# suPino.net
KiCad netlist of a schematic drawn in EAGLE
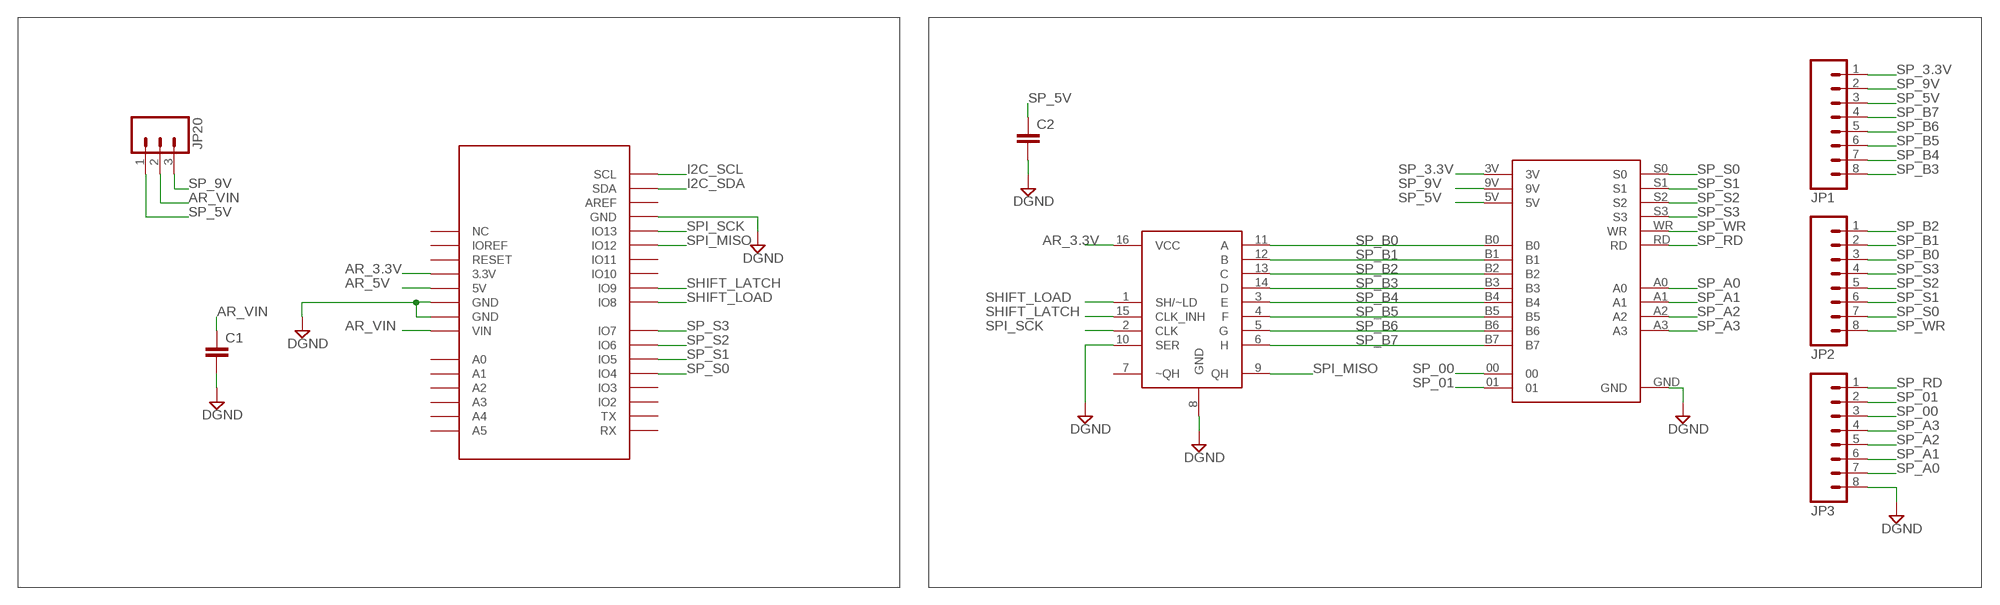
[diagram p0: schematic, sheet 1, part 1 of 2]
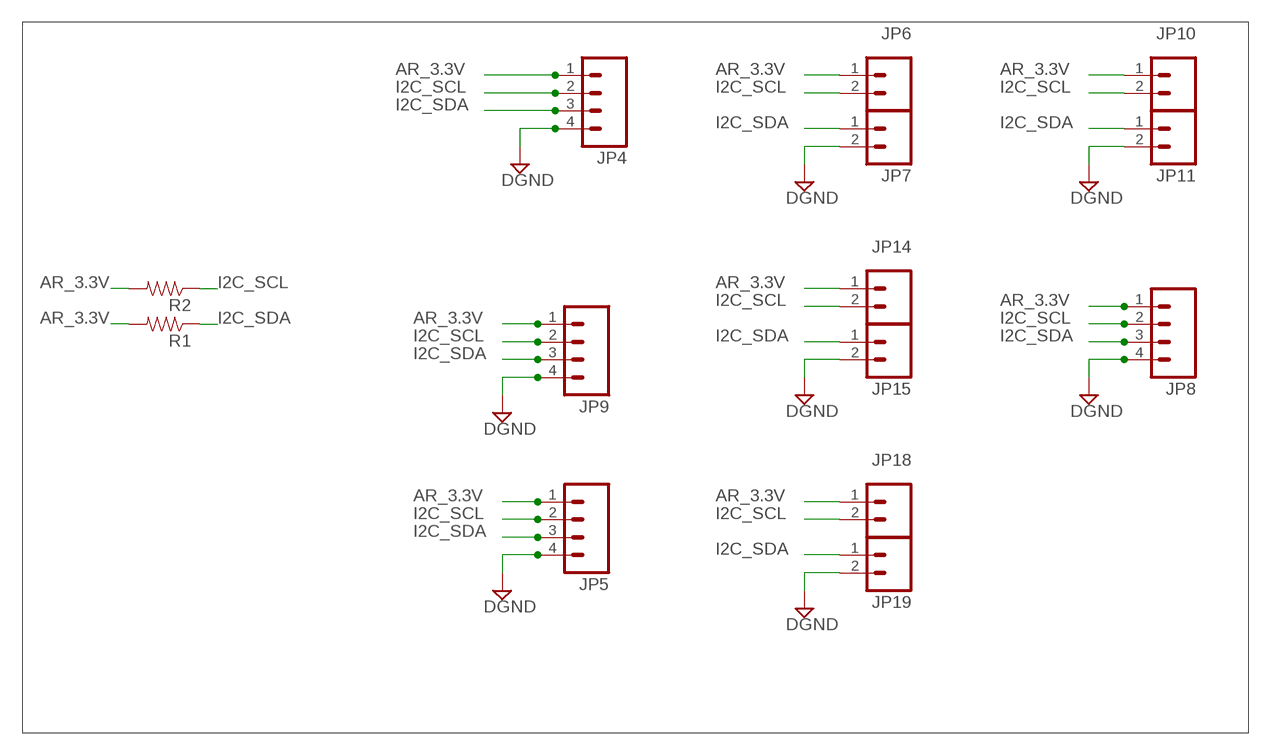
[diagram p1: schematic, sheet 1, part 2 of 2]

(export (version "E")
  (design (tool "Eeschema 10.0.6"))
  (components
    (comp (ref "C1")
      (value "CAP0805")
      (footprint "eagle-import:0805")
      (libsource (lib "eagle-import") (part "CAP0805"))
    )
    (comp (ref "C2")
      (value "CAP0805")
      (footprint "eagle-import:0805")
      (libsource (lib "eagle-import") (part "CAP0805"))
    )
    (comp (ref "JP1")
      (value "M08")
      (footprint "eagle-import:1X08_ROUND")
      (libsource (lib "eagle-import") (part "M08"))
    )
    (comp (ref "JP2")
      (value "M08")
      (footprint "eagle-import:1X08_ROUND")
      (libsource (lib "eagle-import") (part "M08"))
    )
    (comp (ref "JP3")
      (value "M08")
      (footprint "eagle-import:1X08_ROUND")
      (libsource (lib "eagle-import") (part "M08"))
    )
    (comp (ref "JP4")
      (value "M04PTH")
      (footprint "eagle-import:1X04")
      (libsource (lib "eagle-import") (part "M04PTH"))
    )
    (comp (ref "JP5")
      (value "M04PTH")
      (footprint "eagle-import:1X04")
      (libsource (lib "eagle-import") (part "M04PTH"))
    )
    (comp (ref "JP6")
      (value "M023.5MM")
      (footprint "eagle-import:SCREWTERMINAL-3.5MM-2")
      (libsource (lib "eagle-import") (part "M023.5MM"))
    )
    (comp (ref "JP7")
      (value "M023.5MM")
      (footprint "eagle-import:SCREWTERMINAL-3.5MM-2")
      (libsource (lib "eagle-import") (part "M023.5MM"))
    )
    (comp (ref "JP8")
      (value "M04PTH")
      (footprint "eagle-import:1X04")
      (libsource (lib "eagle-import") (part "M04PTH"))
    )
    (comp (ref "JP9")
      (value "M04PTH")
      (footprint "eagle-import:1X04")
      (libsource (lib "eagle-import") (part "M04PTH"))
    )
    (comp (ref "JP10")
      (value "M023.5MM")
      (footprint "eagle-import:SCREWTERMINAL-3.5MM-2")
      (libsource (lib "eagle-import") (part "M023.5MM"))
    )
    (comp (ref "JP11")
      (value "M023.5MM")
      (footprint "eagle-import:SCREWTERMINAL-3.5MM-2")
      (libsource (lib "eagle-import") (part "M023.5MM"))
    )
    (comp (ref "JP14")
      (value "M023.5MM")
      (footprint "eagle-import:SCREWTERMINAL-3.5MM-2")
      (libsource (lib "eagle-import") (part "M023.5MM"))
    )
    (comp (ref "JP15")
      (value "M023.5MM")
      (footprint "eagle-import:SCREWTERMINAL-3.5MM-2")
      (libsource (lib "eagle-import") (part "M023.5MM"))
    )
    (comp (ref "JP18")
      (value "M023.5MM")
      (footprint "eagle-import:SCREWTERMINAL-3.5MM-2")
      (libsource (lib "eagle-import") (part "M023.5MM"))
    )
    (comp (ref "JP19")
      (value "M023.5MM")
      (footprint "eagle-import:SCREWTERMINAL-3.5MM-2")
      (libsource (lib "eagle-import") (part "M023.5MM"))
    )
    (comp (ref "JP20")
      (value "M03PTH")
      (footprint "eagle-import:1X03")
      (libsource (lib "eagle-import") (part "M03PTH"))
    )
    (comp (ref "R1")
      (value "RESISTOR0805-RES")
      (footprint "eagle-import:0805")
      (libsource (lib "eagle-import") (part "RESISTOR0805-RES"))
    )
    (comp (ref "R2")
      (value "RESISTOR0805-RES")
      (footprint "eagle-import:0805")
      (libsource (lib "eagle-import") (part "RESISTOR0805-RES"))
    )
    (comp (ref "U$1")
      (value "ARDUIN_SHIELD")
      (footprint "eagle-import:ARDUNIO_SHIELD")
      (libsource (lib "eagle-import") (part "ARDUIN_SHIELD"))
    )
    (comp (ref "U$2")
      (value "SUPERPRO_BOARD")
      (footprint "eagle-import:SUPERPRO_BOARD")
      (libsource (lib "eagle-import") (part "SUPERPRO_BOARD"))
    )
    (comp (ref "U$4")
      (value "8B_SHIFT_REG")
      (footprint "eagle-import:TSSOP16")
      (libsource (lib "eagle-import") (part "8B_SHIFT_REG"))
    )
  )
  (nets
    (net (code "1") (name "/AR_3.3V") (class "Default")
      (node (ref "JP10") (pin "1") (pinfunction "1_1") (pintype "passive"))
      (node (ref "JP14") (pin "1") (pinfunction "1_1") (pintype "passive"))
      (node (ref "JP18") (pin "1") (pinfunction "1_1") (pintype "passive"))
      (node (ref "JP4") (pin "1") (pinfunction "1_1") (pintype "passive"))
      (node (ref "JP5") (pin "1") (pinfunction "1_1") (pintype "passive"))
      (node (ref "JP6") (pin "1") (pinfunction "1_1") (pintype "passive"))
      (node (ref "JP8") (pin "1") (pinfunction "1_1") (pintype "passive"))
      (node (ref "JP9") (pin "1") (pinfunction "1_1") (pintype "passive"))
      (node (ref "R1") (pin "2") (pinfunction "2_2") (pintype "passive"))
      (node (ref "R2") (pin "2") (pinfunction "2_2") (pintype "passive"))
      (node (ref "U$1") (pin "3.3V") (pinfunction "3.3V_3.3V") (pintype "bidirectional"))
      (node (ref "U$4") (pin "16") (pinfunction "VCC_16") (pintype "bidirectional"))
    )
    (net (code "2") (name "/AR_5V") (class "Default")
      (node (ref "U$1") (pin "5V") (pinfunction "5V_5V") (pintype "bidirectional"))
    )
    (net (code "3") (name "/AR_VIN") (class "Default")
      (node (ref "C1") (pin "1") (pinfunction "1_1") (pintype "passive"))
      (node (ref "JP20") (pin "2") (pinfunction "2_2") (pintype "passive"))
      (node (ref "U$1") (pin "VIN") (pinfunction "VIN_VIN") (pintype "bidirectional"))
    )
    (net (code "4") (name "/I2C_SCL") (class "Default")
      (node (ref "JP10") (pin "2") (pinfunction "2_2") (pintype "passive"))
      (node (ref "JP14") (pin "2") (pinfunction "2_2") (pintype "passive"))
      (node (ref "JP18") (pin "2") (pinfunction "2_2") (pintype "passive"))
      (node (ref "JP4") (pin "2") (pinfunction "2_2") (pintype "passive"))
      (node (ref "JP5") (pin "2") (pinfunction "2_2") (pintype "passive"))
      (node (ref "JP6") (pin "2") (pinfunction "2_2") (pintype "passive"))
      (node (ref "JP8") (pin "2") (pinfunction "2_2") (pintype "passive"))
      (node (ref "JP9") (pin "2") (pinfunction "2_2") (pintype "passive"))
      (node (ref "R2") (pin "1") (pinfunction "1_1") (pintype "passive"))
      (node (ref "U$1") (pin "SCL") (pinfunction "SCL_SCL") (pintype "bidirectional"))
    )
    (net (code "5") (name "/I2C_SDA") (class "Default")
      (node (ref "JP11") (pin "1") (pinfunction "1_1") (pintype "passive"))
      (node (ref "JP15") (pin "1") (pinfunction "1_1") (pintype "passive"))
      (node (ref "JP19") (pin "1") (pinfunction "1_1") (pintype "passive"))
      (node (ref "JP4") (pin "3") (pinfunction "3_3") (pintype "passive"))
      (node (ref "JP5") (pin "3") (pinfunction "3_3") (pintype "passive"))
      (node (ref "JP7") (pin "1") (pinfunction "1_1") (pintype "passive"))
      (node (ref "JP8") (pin "3") (pinfunction "3_3") (pintype "passive"))
      (node (ref "JP9") (pin "3") (pinfunction "3_3") (pintype "passive"))
      (node (ref "R1") (pin "1") (pinfunction "1_1") (pintype "passive"))
      (node (ref "U$1") (pin "SDA") (pinfunction "SDA_SDA") (pintype "bidirectional"))
    )
    (net (code "6") (name "/SHIFT_LATCH") (class "Default")
      (node (ref "U$1") (pin "IO9") (pinfunction "IO9_IO9") (pintype "bidirectional"))
      (node (ref "U$4") (pin "15") (pinfunction "CLK_INH_15") (pintype "bidirectional"))
    )
    (net (code "7") (name "/SHIFT_LOAD") (class "Default")
      (node (ref "U$1") (pin "IO8") (pinfunction "IO8_IO8") (pintype "bidirectional"))
      (node (ref "U$4") (pin "1") (pinfunction "SH/~{LD}_1") (pintype "bidirectional"))
    )
    (net (code "8") (name "/SPI_MISO") (class "Default")
      (node (ref "U$1") (pin "IO12") (pinfunction "IO12_IO12") (pintype "bidirectional"))
      (node (ref "U$4") (pin "9") (pinfunction "QH_9") (pintype "bidirectional"))
    )
    (net (code "9") (name "/SPI_SCK") (class "Default")
      (node (ref "U$1") (pin "IO13") (pinfunction "IO13_IO13") (pintype "bidirectional"))
      (node (ref "U$4") (pin "2") (pinfunction "CLK_2") (pintype "bidirectional"))
    )
    (net (code "10") (name "/SP_00") (class "Default")
      (node (ref "JP3") (pin "3") (pinfunction "3_3") (pintype "passive"))
      (node (ref "U$2") (pin "00") (pinfunction "00_00") (pintype "bidirectional"))
    )
    (net (code "11") (name "/SP_01") (class "Default")
      (node (ref "JP3") (pin "2") (pinfunction "2_2") (pintype "passive"))
      (node (ref "U$2") (pin "01") (pinfunction "01_01") (pintype "bidirectional"))
    )
    (net (code "12") (name "/SP_3.3V") (class "Default")
      (node (ref "JP1") (pin "1") (pinfunction "1_1") (pintype "passive"))
      (node (ref "U$2") (pin "3V") (pinfunction "3V_3V") (pintype "bidirectional"))
    )
    (net (code "13") (name "/SP_5V") (class "Default")
      (node (ref "C2") (pin "1") (pinfunction "1_1") (pintype "passive"))
      (node (ref "JP1") (pin "3") (pinfunction "3_3") (pintype "passive"))
      (node (ref "JP20") (pin "1") (pinfunction "1_1") (pintype "passive"))
      (node (ref "U$2") (pin "5V") (pinfunction "5V_5V") (pintype "bidirectional"))
    )
    (net (code "14") (name "/SP_9V") (class "Default")
      (node (ref "JP1") (pin "2") (pinfunction "2_2") (pintype "passive"))
      (node (ref "JP20") (pin "3") (pinfunction "3_3") (pintype "passive"))
      (node (ref "U$2") (pin "9V") (pinfunction "9V_9V") (pintype "bidirectional"))
    )
    (net (code "15") (name "/SP_A0") (class "Default")
      (node (ref "JP3") (pin "7") (pinfunction "7_7") (pintype "passive"))
      (node (ref "U$2") (pin "A0") (pinfunction "A0_A0") (pintype "bidirectional"))
    )
    (net (code "16") (name "/SP_A1") (class "Default")
      (node (ref "JP3") (pin "6") (pinfunction "6_6") (pintype "passive"))
      (node (ref "U$2") (pin "A1") (pinfunction "A1_A1") (pintype "bidirectional"))
    )
    (net (code "17") (name "/SP_A2") (class "Default")
      (node (ref "JP3") (pin "5") (pinfunction "5_5") (pintype "passive"))
      (node (ref "U$2") (pin "A2") (pinfunction "A2_A2") (pintype "bidirectional"))
    )
    (net (code "18") (name "/SP_A3") (class "Default")
      (node (ref "JP3") (pin "4") (pinfunction "4_4") (pintype "passive"))
      (node (ref "U$2") (pin "A3") (pinfunction "A3_A3") (pintype "bidirectional"))
    )
    (net (code "19") (name "/SP_B0") (class "Default")
      (node (ref "JP2") (pin "3") (pinfunction "3_3") (pintype "passive"))
      (node (ref "U$2") (pin "B0") (pinfunction "B0_B0") (pintype "bidirectional"))
      (node (ref "U$4") (pin "11") (pinfunction "A_11") (pintype "bidirectional"))
    )
    (net (code "20") (name "/SP_B1") (class "Default")
      (node (ref "JP2") (pin "2") (pinfunction "2_2") (pintype "passive"))
      (node (ref "U$2") (pin "B1") (pinfunction "B1_B1") (pintype "bidirectional"))
      (node (ref "U$4") (pin "12") (pinfunction "B_12") (pintype "bidirectional"))
    )
    (net (code "21") (name "/SP_B2") (class "Default")
      (node (ref "JP2") (pin "1") (pinfunction "1_1") (pintype "passive"))
      (node (ref "U$2") (pin "B2") (pinfunction "B2_B2") (pintype "bidirectional"))
      (node (ref "U$4") (pin "13") (pinfunction "C_13") (pintype "bidirectional"))
    )
    (net (code "22") (name "/SP_B3") (class "Default")
      (node (ref "JP1") (pin "8") (pinfunction "8_8") (pintype "passive"))
      (node (ref "U$2") (pin "B3") (pinfunction "B3_B3") (pintype "bidirectional"))
      (node (ref "U$4") (pin "14") (pinfunction "D_14") (pintype "bidirectional"))
    )
    (net (code "23") (name "/SP_B4") (class "Default")
      (node (ref "JP1") (pin "7") (pinfunction "7_7") (pintype "passive"))
      (node (ref "U$2") (pin "B4") (pinfunction "B4_B4") (pintype "bidirectional"))
      (node (ref "U$4") (pin "3") (pinfunction "E_3") (pintype "bidirectional"))
    )
    (net (code "24") (name "/SP_B5") (class "Default")
      (node (ref "JP1") (pin "6") (pinfunction "6_6") (pintype "passive"))
      (node (ref "U$2") (pin "B5") (pinfunction "B5_B5") (pintype "bidirectional"))
      (node (ref "U$4") (pin "4") (pinfunction "F_4") (pintype "bidirectional"))
    )
    (net (code "25") (name "/SP_B6") (class "Default")
      (node (ref "JP1") (pin "5") (pinfunction "5_5") (pintype "passive"))
      (node (ref "U$2") (pin "B6") (pinfunction "B6_B6") (pintype "bidirectional"))
      (node (ref "U$4") (pin "5") (pinfunction "G_5") (pintype "bidirectional"))
    )
    (net (code "26") (name "/SP_B7") (class "Default")
      (node (ref "JP1") (pin "4") (pinfunction "4_4") (pintype "passive"))
      (node (ref "U$2") (pin "B7") (pinfunction "B7_B7") (pintype "bidirectional"))
      (node (ref "U$4") (pin "6") (pinfunction "H_6") (pintype "bidirectional"))
    )
    (net (code "27") (name "/SP_RD") (class "Default")
      (node (ref "JP3") (pin "1") (pinfunction "1_1") (pintype "passive"))
      (node (ref "U$2") (pin "RD") (pinfunction "RD_RD") (pintype "bidirectional"))
    )
    (net (code "28") (name "/SP_S0") (class "Default")
      (node (ref "JP2") (pin "7") (pinfunction "7_7") (pintype "passive"))
      (node (ref "U$1") (pin "IO4") (pinfunction "IO4_IO4") (pintype "bidirectional"))
      (node (ref "U$2") (pin "S0") (pinfunction "S0_S0") (pintype "bidirectional"))
    )
    (net (code "29") (name "/SP_S1") (class "Default")
      (node (ref "JP2") (pin "6") (pinfunction "6_6") (pintype "passive"))
      (node (ref "U$1") (pin "IO5") (pinfunction "IO5_IO5") (pintype "bidirectional"))
      (node (ref "U$2") (pin "S1") (pinfunction "S1_S1") (pintype "bidirectional"))
    )
    (net (code "30") (name "/SP_S2") (class "Default")
      (node (ref "JP2") (pin "5") (pinfunction "5_5") (pintype "passive"))
      (node (ref "U$1") (pin "IO6") (pinfunction "IO6_IO6") (pintype "bidirectional"))
      (node (ref "U$2") (pin "S2") (pinfunction "S2_S2") (pintype "bidirectional"))
    )
    (net (code "31") (name "/SP_S3") (class "Default")
      (node (ref "JP2") (pin "4") (pinfunction "4_4") (pintype "passive"))
      (node (ref "U$1") (pin "IO7") (pinfunction "IO7_IO7") (pintype "bidirectional"))
      (node (ref "U$2") (pin "S3") (pinfunction "S3_S3") (pintype "bidirectional"))
    )
    (net (code "32") (name "/SP_WR") (class "Default")
      (node (ref "JP2") (pin "8") (pinfunction "8_8") (pintype "passive"))
      (node (ref "U$2") (pin "WR") (pinfunction "WR_WR") (pintype "bidirectional"))
    )
    (net (code "33") (name "DGND") (class "Default")
      (node (ref "C1") (pin "2") (pinfunction "2_2") (pintype "passive"))
      (node (ref "C2") (pin "2") (pinfunction "2_2") (pintype "passive"))
      (node (ref "JP11") (pin "2") (pinfunction "2_2") (pintype "passive"))
      (node (ref "JP15") (pin "2") (pinfunction "2_2") (pintype "passive"))
      (node (ref "JP19") (pin "2") (pinfunction "2_2") (pintype "passive"))
      (node (ref "JP3") (pin "8") (pinfunction "8_8") (pintype "passive"))
      (node (ref "JP4") (pin "4") (pinfunction "4_4") (pintype "passive"))
      (node (ref "JP5") (pin "4") (pinfunction "4_4") (pintype "passive"))
      (node (ref "JP7") (pin "2") (pinfunction "2_2") (pintype "passive"))
      (node (ref "JP8") (pin "4") (pinfunction "4_4") (pintype "passive"))
      (node (ref "JP9") (pin "4") (pinfunction "4_4") (pintype "passive"))
      (node (ref "U$1") (pin "GND@0") (pinfunction "GND_GND@0") (pintype "bidirectional"))
      (node (ref "U$1") (pin "GND@1") (pinfunction "GND_GND@1") (pintype "bidirectional"))
      (node (ref "U$1") (pin "GND@2") (pinfunction "GND_GND@2") (pintype "bidirectional"))
      (node (ref "U$2") (pin "GND") (pinfunction "GND_GND") (pintype "bidirectional"))
      (node (ref "U$4") (pin "10") (pinfunction "SER_10") (pintype "bidirectional"))
      (node (ref "U$4") (pin "8") (pinfunction "GND_8") (pintype "bidirectional"))
    )
    (net (code "34") (name "unconnected-(U$1-NC-PadN{slash}C)") (class "Default")
      (node (ref "U$1") (pin "N/C") (pinfunction "NC_N/C") (pintype "bidirectional"))
    )
    (net (code "35") (name "unconnected-(U$1-PadA0)") (class "Default")
      (node (ref "U$1") (pin "A0") (pinfunction "A0_A0") (pintype "bidirectional"))
    )
    (net (code "36") (name "unconnected-(U$1-PadA1)") (class "Default")
      (node (ref "U$1") (pin "A1") (pinfunction "A1_A1") (pintype "bidirectional"))
    )
    (net (code "37") (name "unconnected-(U$1-PadA2)") (class "Default")
      (node (ref "U$1") (pin "A2") (pinfunction "A2_A2") (pintype "bidirectional"))
    )
    (net (code "38") (name "unconnected-(U$1-PadA3)") (class "Default")
      (node (ref "U$1") (pin "A3") (pinfunction "A3_A3") (pintype "bidirectional"))
    )
    (net (code "39") (name "unconnected-(U$1-PadA4)") (class "Default")
      (node (ref "U$1") (pin "A4") (pinfunction "A4_A4") (pintype "bidirectional"))
    )
    (net (code "40") (name "unconnected-(U$1-PadA5)") (class "Default")
      (node (ref "U$1") (pin "A5") (pinfunction "A5_A5") (pintype "bidirectional"))
    )
    (net (code "41") (name "unconnected-(U$1-PadAREF)") (class "Default")
      (node (ref "U$1") (pin "AREF") (pinfunction "AREF_AREF") (pintype "bidirectional"))
    )
    (net (code "42") (name "unconnected-(U$1-PadIO2)") (class "Default")
      (node (ref "U$1") (pin "IO2") (pinfunction "IO2_IO2") (pintype "bidirectional"))
    )
    (net (code "43") (name "unconnected-(U$1-PadIO3)") (class "Default")
      (node (ref "U$1") (pin "IO3") (pinfunction "IO3_IO3") (pintype "bidirectional"))
    )
    (net (code "44") (name "unconnected-(U$1-PadIO10)") (class "Default")
      (node (ref "U$1") (pin "IO10") (pinfunction "IO10_IO10") (pintype "bidirectional"))
    )
    (net (code "45") (name "unconnected-(U$1-PadIO11)") (class "Default")
      (node (ref "U$1") (pin "IO11") (pinfunction "IO11_IO11") (pintype "bidirectional"))
    )
    (net (code "46") (name "unconnected-(U$1-PadIOREF)") (class "Default")
      (node (ref "U$1") (pin "IOREF") (pinfunction "IOREF_IOREF") (pintype "bidirectional"))
    )
    (net (code "47") (name "unconnected-(U$1-PadRESET)") (class "Default")
      (node (ref "U$1") (pin "RESET") (pinfunction "RESET_RESET") (pintype "bidirectional"))
    )
    (net (code "48") (name "unconnected-(U$1-PadRX)") (class "Default")
      (node (ref "U$1") (pin "RX") (pinfunction "RX_RX") (pintype "bidirectional"))
    )
    (net (code "49") (name "unconnected-(U$1-PadTX)") (class "Default")
      (node (ref "U$1") (pin "TX") (pinfunction "TX_TX") (pintype "bidirectional"))
    )
    (net (code "50") (name "unconnected-(U$4-~{QH}-Pad7)") (class "Default")
      (node (ref "U$4") (pin "7") (pinfunction "~{QH}_7") (pintype "bidirectional"))
    )
  )
)
